# ACPowerDistributionFanControl.net
KiCad netlist of a schematic drawn in Altium Designer
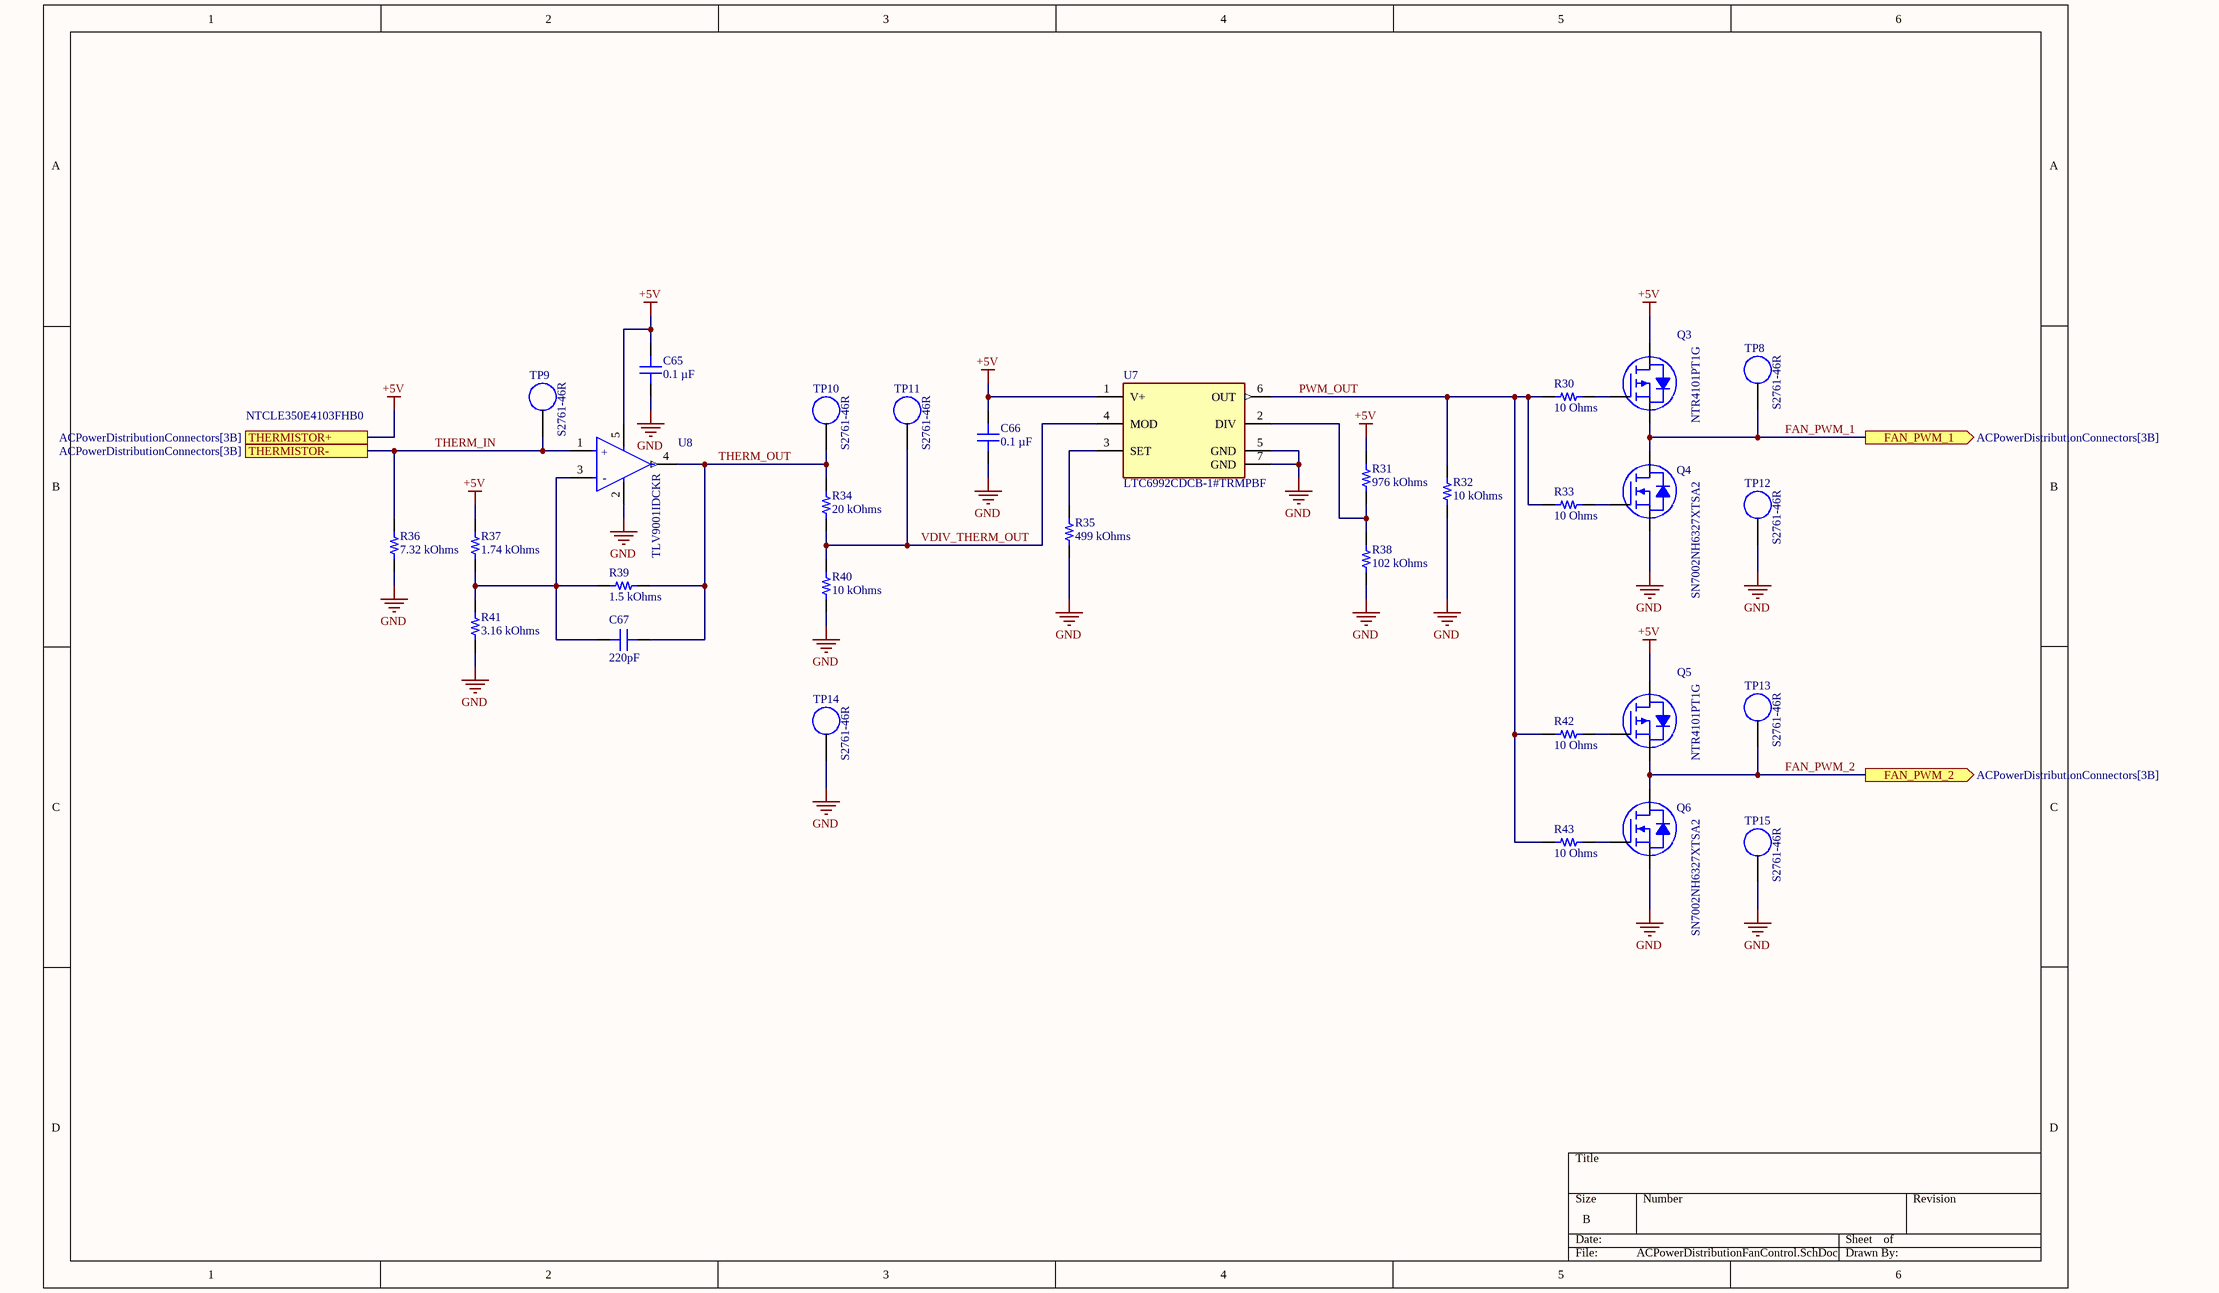
[diagram p0: ACPowerDistributionFanControl.SchDoc]

(export (version "E")
  (design (tool "Eeschema 10.0.6"))
  (components
    (comp (ref "C65")
      (value "0.1 µF")
      (footprint "CAP 0603_1608")
      (description "CAP CER 0.1UF 25V X7R 0603")
      (fields
        (field (name "PART NUMBER") "CL10B104KA8WPNC")
        (field (name "CAPACITANCE") "0.1 µF")
        (field (name "MANUFACTURER") "Samsung Electro-Mechanics")
      )
      (libsource (lib "Celestial Altium Library - altium_library") (part "Capacitor"))
    )
    (comp (ref "C66")
      (value "0.1 µF")
      (footprint "CAP 0603_1608")
      (description "CAP CER 0.1UF 25V X7R 0603")
      (fields
        (field (name "PART NUMBER") "CL10B104KA8WPNC")
        (field (name "CAPACITANCE") "0.1 µF")
        (field (name "MANUFACTURER") "Samsung Electro-Mechanics")
      )
      (libsource (lib "Celestial Altium Library - altium_library") (part "Capacitor"))
    )
    (comp (ref "C67")
      (value "220pF")
      (footprint "CAP 0603_1608")
      (description "CAP CER 220PF 25V C0G/NP0 0603")
      (fields
        (field (name "PART NUMBER") "06033A221KAT2A")
        (field (name "CAPACITANCE") "220pF")
        (field (name "MANUFACTURER") "AVX Corporation")
      )
      (libsource (lib "Celestial Altium Library - altium_library") (part "Capacitor"))
    )
    (comp (ref "Q3")
      (value "NTR4101PT1G")
      (footprint "ON SEMI SOT-23-3")
      (description "MOSFET P-CH 20V 1.8A SOT-23")
      (fields (field (name "MANUFACTURER") "ON Semiconductor"))
      (libsource (lib "Celestial Altium Library - altium_library") (part "ON SEMI MOSFET P-CH SOT-23-3"))
    )
    (comp (ref "Q4")
      (value "SN7002NH6327XTSA2")
      (footprint "INFINEON SOT-23-3")
      (description "MOSFET N-CH 60V 200MA SOT23-3")
      (fields (field (name "MANUFACTURER") "Infineon Technologies"))
      (libsource (lib "Celestial Altium Library - altium_library") (part "INFINEON MOSFET N-CH SOT-23-3 GSD"))
    )
    (comp (ref "Q5")
      (value "NTR4101PT1G")
      (footprint "ON SEMI SOT-23-3")
      (description "MOSFET P-CH 20V 1.8A SOT-23")
      (fields (field (name "MANUFACTURER") "ON Semiconductor"))
      (libsource (lib "Celestial Altium Library - altium_library") (part "ON SEMI MOSFET P-CH SOT-23-3"))
    )
    (comp (ref "Q6")
      (value "SN7002NH6327XTSA2")
      (footprint "INFINEON SOT-23-3")
      (description "MOSFET N-CH 60V 200MA SOT23-3")
      (fields (field (name "MANUFACTURER") "Infineon Technologies"))
      (libsource (lib "Celestial Altium Library - altium_library") (part "INFINEON MOSFET N-CH SOT-23-3 GSD"))
    )
    (comp (ref "R30")
      (value "10 Ohms")
      (footprint "RES 0603_1608")
      (description "RES 10 OHM 1% 1/10W 0603")
      (fields
        (field (name "PART NUMBER") "RMCF0603FT10R0")
        (field (name "MANUFACTURER") "Stackpole Electronics Inc")
      )
      (libsource (lib "Celestial Altium Library - altium_library") (part "Resistor"))
    )
    (comp (ref "R31")
      (value "976 kOhms")
      (footprint "RES 0603_1608")
      (description "RES 976K OHM 1% 1/10W 0603")
      (fields
        (field (name "PART NUMBER") "RMCF0603FT976K")
        (field (name "MANUFACTURER") "Stackpole Electronics Inc")
      )
      (libsource (lib "Celestial Altium Library - altium_library") (part "Resistor"))
    )
    (comp (ref "R32")
      (value "10 kOhms")
      (footprint "RES 0603_1608")
      (description "RES 10K OHM 1% 1/10W 0603")
      (fields
        (field (name "PART NUMBER") "RMCF0603FT10K0")
        (field (name "MANUFACTURER") "Stackpole Electronics Inc")
      )
      (libsource (lib "Celestial Altium Library - altium_library") (part "Resistor"))
    )
    (comp (ref "R33")
      (value "10 Ohms")
      (footprint "RES 0603_1608")
      (description "RES 10 OHM 1% 1/10W 0603")
      (fields
        (field (name "PART NUMBER") "RMCF0603FT10R0")
        (field (name "MANUFACTURER") "Stackpole Electronics Inc")
      )
      (libsource (lib "Celestial Altium Library - altium_library") (part "Resistor"))
    )
    (comp (ref "R34")
      (value "20 kOhms")
      (footprint "RES 0603_1608")
      (description "RES SMD 20K OHM 0.1% 1/6W 0603")
      (fields
        (field (name "PART NUMBER") "RNCF0603BTC20K0")
        (field (name "MANUFACTURER") "Stackpole Electronics Inc")
      )
      (libsource (lib "Celestial Altium Library - altium_library") (part "Resistor"))
    )
    (comp (ref "R35")
      (value "499 kOhms")
      (footprint "RES 0603_1608")
      (description "RES 499K OHM 1% 1/10W 0603")
      (fields
        (field (name "PART NUMBER") "RMCF0603FT499K")
        (field (name "MANUFACTURER") "Stackpole Electronics Inc")
      )
      (libsource (lib "Celestial Altium Library - altium_library") (part "Resistor"))
    )
    (comp (ref "R36")
      (value "7.32 kOhms")
      (footprint "RES 0603_1608")
      (description "RES SMD 7.32KOHM 0.1% 1/10W 0603")
      (fields
        (field (name "PART NUMBER") "ERA-3AEB7321V")
        (field (name "MANUFACTURER") "Panasonic Electronic Components")
      )
      (libsource (lib "Celestial Altium Library - altium_library") (part "Resistor"))
    )
    (comp (ref "R37")
      (value "1.74 kOhms")
      (footprint "RES 0603_1608")
      (description "RES SMD 1.74KOHM 0.1% 1/10W 0603")
      (fields
        (field (name "PART NUMBER") "ERA-3AEB1741V")
        (field (name "MANUFACTURER") "Panasonic Electronic Components")
      )
      (libsource (lib "Celestial Altium Library - altium_library") (part "Resistor"))
    )
    (comp (ref "R38")
      (value "102 kOhms")
      (footprint "RES 0603_1608")
      (description "RES 102K OHM 1% 1/10W 0603")
      (fields
        (field (name "PART NUMBER") "RMCF0603FG102K")
        (field (name "MANUFACTURER") "Stackpole Electronics Inc")
      )
      (libsource (lib "Celestial Altium Library - altium_library") (part "Resistor"))
    )
    (comp (ref "R39")
      (value "1.5 kOhms")
      (footprint "RES 0603_1608")
      (description "RES 1.5K OHM 0.1% 1/16W 0603")
      (fields
        (field (name "PART NUMBER") "RNCS0603BKE1K50")
        (field (name "MANUFACTURER") "Stackpole Electronics Inc")
      )
      (libsource (lib "Celestial Altium Library - altium_library") (part "Resistor"))
    )
    (comp (ref "R40")
      (value "10 kOhms")
      (footprint "RES 0603_1608")
      (description "RES SMD 10K OHM 0.1% 1/6W 0603")
      (fields
        (field (name "PART NUMBER") "RNCF0603BTE10K0")
        (field (name "MANUFACTURER") "Stackpole Electronics Inc")
      )
      (libsource (lib "Celestial Altium Library - altium_library") (part "Resistor"))
    )
    (comp (ref "R41")
      (value "3.16 kOhms")
      (footprint "RES 0603_1608")
      (description "RES SMD 3.16KOHM 0.1% 1/10W 0603")
      (fields
        (field (name "PART NUMBER") "ERA-3AEB3161V")
        (field (name "MANUFACTURER") "Panasonic Electronic Components")
      )
      (libsource (lib "Celestial Altium Library - altium_library") (part "Resistor"))
    )
    (comp (ref "R42")
      (value "10 Ohms")
      (footprint "RES 0603_1608")
      (description "RES 10 OHM 1% 1/10W 0603")
      (fields
        (field (name "PART NUMBER") "RMCF0603FT10R0")
        (field (name "MANUFACTURER") "Stackpole Electronics Inc")
      )
      (libsource (lib "Celestial Altium Library - altium_library") (part "Resistor"))
    )
    (comp (ref "R43")
      (value "10 Ohms")
      (footprint "RES 0603_1608")
      (description "RES 10 OHM 1% 1/10W 0603")
      (fields
        (field (name "PART NUMBER") "RMCF0603FT10R0")
        (field (name "MANUFACTURER") "Stackpole Electronics Inc")
      )
      (libsource (lib "Celestial Altium Library - altium_library") (part "Resistor"))
    )
    (comp (ref "TP8")
      (value "S2761-46R")
      (footprint "S2761-46R")
      (libsource (lib "PersonalLibrary") (part "S2761-46R"))
    )
    (comp (ref "TP9")
      (value "S2761-46R")
      (footprint "S2761-46R")
      (libsource (lib "PersonalLibrary") (part "S2761-46R"))
    )
    (comp (ref "TP10")
      (value "S2761-46R")
      (footprint "S2761-46R")
      (libsource (lib "PersonalLibrary") (part "S2761-46R"))
    )
    (comp (ref "TP11")
      (value "S2761-46R")
      (footprint "S2761-46R")
      (libsource (lib "PersonalLibrary") (part "S2761-46R"))
    )
    (comp (ref "TP12")
      (value "S2761-46R")
      (footprint "S2761-46R")
      (libsource (lib "PersonalLibrary") (part "S2761-46R"))
    )
    (comp (ref "TP13")
      (value "S2761-46R")
      (footprint "S2761-46R")
      (libsource (lib "PersonalLibrary") (part "S2761-46R"))
    )
    (comp (ref "TP14")
      (value "S2761-46R")
      (footprint "S2761-46R")
      (libsource (lib "PersonalLibrary") (part "S2761-46R"))
    )
    (comp (ref "TP15")
      (value "S2761-46R")
      (footprint "S2761-46R")
      (libsource (lib "PersonalLibrary") (part "S2761-46R"))
    )
    (comp (ref "U7")
      (value "LTC6992CDCB-1#TRMPBF")
      (footprint "FP-DCB-6-05-08-1715-MFG")
      (description "IC OSC SILICON PROG 6-DFN")
      (libsource (lib "Altium Content Vault") (part "e4f96c068363ec00df2eaba9be5011b"))
    )
    (comp (ref "U8")
      (value "TLV9001IDCKR")
      (footprint "FP-DCK0005A-MFG")
      (description "IC CMOS 1 CIRCUIT SC70-5")
      (libsource (lib "Altium Content Vault") (part "471d8b929410cd356ad4b122f572ce5"))
    )
  )
  (nets
    (net (code "1") (name "+5V") (class "Default")
      (node (ref "C65") (pin "2") (pinfunction "2_2") (pintype "passive"))
      (node (ref "C66") (pin "2") (pinfunction "2_2") (pintype "passive"))
      (node (ref "Q3") (pin "3") (pinfunction "D_3") (pintype "passive"))
      (node (ref "Q5") (pin "3") (pinfunction "D_3") (pintype "passive"))
      (node (ref "R31") (pin "2") (pinfunction "2_2") (pintype "passive"))
      (node (ref "R37") (pin "2") (pinfunction "2_2") (pintype "passive"))
      (node (ref "U7") (pin "1") (pinfunction "V+_1") (pintype "power_in"))
      (node (ref "U8") (pin "5") (pinfunction "V+_5") (pintype "power_in"))
    )
    (net (code "2") (name "/FAN_PWM_1") (class "Default")
      (node (ref "Q3") (pin "2") (pinfunction "S_2") (pintype "passive"))
      (node (ref "Q4") (pin "3") (pinfunction "D_3") (pintype "passive"))
      (node (ref "TP8") (pin "1") (pinfunction "1_1") (pintype "passive"))
    )
    (net (code "3") (name "/FAN_PWM_2") (class "Default")
      (node (ref "Q5") (pin "2") (pinfunction "S_2") (pintype "passive"))
      (node (ref "Q6") (pin "3") (pinfunction "D_3") (pintype "passive"))
      (node (ref "TP13") (pin "1") (pinfunction "1_1") (pintype "passive"))
    )
    (net (code "4") (name "/PWM_OUT") (class "Default")
      (node (ref "R30") (pin "1") (pinfunction "1_1") (pintype "passive"))
      (node (ref "R32") (pin "2") (pinfunction "2_2") (pintype "passive"))
      (node (ref "R33") (pin "1") (pinfunction "1_1") (pintype "passive"))
      (node (ref "R42") (pin "1") (pinfunction "1_1") (pintype "passive"))
      (node (ref "R43") (pin "1") (pinfunction "1_1") (pintype "passive"))
      (node (ref "U7") (pin "6") (pinfunction "OUT_6") (pintype "output"))
    )
    (net (code "5") (name "/THERM_IN") (class "Default")
      (node (ref "R36") (pin "2") (pinfunction "2_2") (pintype "passive"))
      (node (ref "TP9") (pin "1") (pinfunction "1_1") (pintype "passive"))
      (node (ref "U8") (pin "1") (pinfunction "IN+_1") (pintype "tri_state"))
    )
    (net (code "6") (name "/THERM_OUT") (class "Default")
      (node (ref "C67") (pin "2") (pinfunction "2_2") (pintype "passive"))
      (node (ref "R34") (pin "2") (pinfunction "2_2") (pintype "passive"))
      (node (ref "R39") (pin "2") (pinfunction "2_2") (pintype "passive"))
      (node (ref "TP10") (pin "1") (pinfunction "1_1") (pintype "passive"))
      (node (ref "U8") (pin "4") (pinfunction "OUT_4") (pintype "output"))
    )
    (net (code "7") (name "/VDIV_THERM_OUT") (class "Default")
      (node (ref "R34") (pin "1") (pinfunction "1_1") (pintype "passive"))
      (node (ref "R40") (pin "2") (pinfunction "2_2") (pintype "passive"))
      (node (ref "TP11") (pin "1") (pinfunction "1_1") (pintype "passive"))
      (node (ref "U7") (pin "4") (pinfunction "MOD_4") (pintype "passive"))
    )
    (net (code "8") (name "GND") (class "Default")
      (node (ref "C65") (pin "1") (pinfunction "1_1") (pintype "passive"))
      (node (ref "C66") (pin "1") (pinfunction "1_1") (pintype "passive"))
      (node (ref "Q4") (pin "2") (pinfunction "S_2") (pintype "passive"))
      (node (ref "Q6") (pin "2") (pinfunction "S_2") (pintype "passive"))
      (node (ref "R32") (pin "1") (pinfunction "1_1") (pintype "passive"))
      (node (ref "R35") (pin "1") (pinfunction "1_1") (pintype "passive"))
      (node (ref "R36") (pin "1") (pinfunction "1_1") (pintype "passive"))
      (node (ref "R38") (pin "1") (pinfunction "1_1") (pintype "passive"))
      (node (ref "R40") (pin "1") (pinfunction "1_1") (pintype "passive"))
      (node (ref "R41") (pin "1") (pinfunction "1_1") (pintype "passive"))
      (node (ref "TP12") (pin "1") (pinfunction "1_1") (pintype "passive"))
      (node (ref "TP14") (pin "1") (pinfunction "1_1") (pintype "passive"))
      (node (ref "TP15") (pin "1") (pinfunction "1_1") (pintype "passive"))
      (node (ref "U7") (pin "5") (pinfunction "GND_5") (pintype "power_in"))
      (node (ref "U7") (pin "7") (pinfunction "GND_7") (pintype "power_in"))
      (node (ref "U8") (pin "2") (pinfunction "V-_2") (pintype "power_in"))
    )
    (net (code "9") (name "Net-(Q3-G)") (class "Default")
      (node (ref "Q3") (pin "1") (pinfunction "G_1") (pintype "passive"))
      (node (ref "R30") (pin "2") (pinfunction "2_2") (pintype "passive"))
    )
    (net (code "10") (name "Net-(Q4-G)") (class "Default")
      (node (ref "Q4") (pin "1") (pinfunction "G_1") (pintype "passive"))
      (node (ref "R33") (pin "2") (pinfunction "2_2") (pintype "passive"))
    )
    (net (code "11") (name "Net-(Q5-G)") (class "Default")
      (node (ref "Q5") (pin "1") (pinfunction "G_1") (pintype "passive"))
      (node (ref "R42") (pin "2") (pinfunction "2_2") (pintype "passive"))
    )
    (net (code "12") (name "Net-(Q6-G)") (class "Default")
      (node (ref "Q6") (pin "1") (pinfunction "G_1") (pintype "passive"))
      (node (ref "R43") (pin "2") (pinfunction "2_2") (pintype "passive"))
    )
    (net (code "13") (name "Net-(U7-DIV)") (class "Default")
      (node (ref "R31") (pin "1") (pinfunction "1_1") (pintype "passive"))
      (node (ref "R38") (pin "2") (pinfunction "2_2") (pintype "passive"))
      (node (ref "U7") (pin "2") (pinfunction "DIV_2") (pintype "passive"))
    )
    (net (code "14") (name "Net-(U7-SET)") (class "Default")
      (node (ref "R35") (pin "2") (pinfunction "2_2") (pintype "passive"))
      (node (ref "U7") (pin "3") (pinfunction "SET_3") (pintype "passive"))
    )
    (net (code "15") (name "Net-(U8-IN-)") (class "Default")
      (node (ref "C67") (pin "1") (pinfunction "1_1") (pintype "passive"))
      (node (ref "R37") (pin "1") (pinfunction "1_1") (pintype "passive"))
      (node (ref "R39") (pin "1") (pinfunction "1_1") (pintype "passive"))
      (node (ref "R41") (pin "2") (pinfunction "2_2") (pintype "passive"))
      (node (ref "U8") (pin "3") (pinfunction "IN-_3") (pintype "tri_state"))
    )
  )
)
